# 2EDL23.net
KiCad netlist of a schematic drawn in Altium Designer
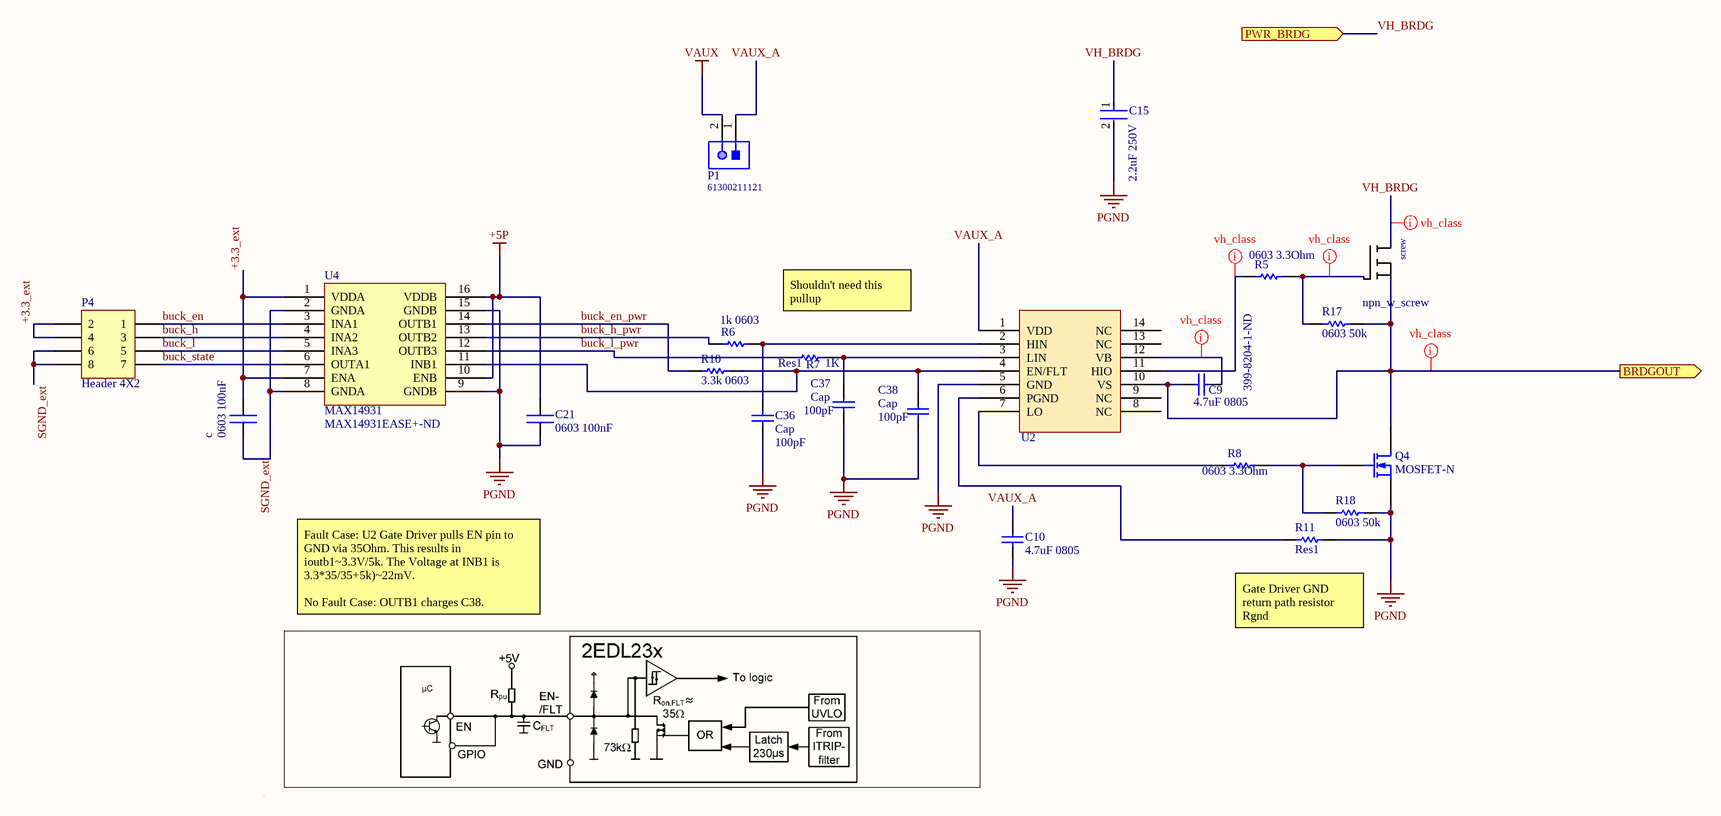
[diagram p0: 2EDL23.SchDoc]

(export (version "E")
  (design (tool "Eeschema 10.0.6"))
  (components
    (comp (ref "c")
      (value "0603 100nF")
      (footprint "CAP 0603_1608")
      (libsource (lib "coil_driver_lib") (part "cap_smd"))
    )
    (comp (ref "C9")
      (value "4.7uF 0805")
      (footprint "CAP 1206_3216 - 0.8MM")
      (description "Capacitor")
      (fields
        (field (name "SUPPLIER PART NUMBER 1") "399-8204-1-ND")
        (field (name "PUBLISHER") "Altium Limited")
      )
      (libsource (lib "Miscellaneous Devices") (part "Cap"))
    )
    (comp (ref "C10")
      (value "4.7uF 0805")
      (footprint "CAP 0805_2012")
      (description "Capacitor")
      (fields (field (name "PUBLISHER") "Altium Limited"))
      (libsource (lib "Miscellaneous Devices") (part "Cap"))
    )
    (comp (ref "C15")
      (value "2.2uF 250V")
      (footprint "FP-CGA9P-IPC_B")
      (description "Cap Ceramic 2.2uF 250V X7T 20% Pad SMD 2220 +125°C Automotive T/R\r\nCGA9P3X7T2E225M250KE")
      (fields (field (name "TOLERANCE") "20%"))
      (libsource (lib "Altium Content Vault") (part "b4654b650e69147ec39a6b967a45e02"))
    )
    (comp (ref "C21")
      (value "0603 100nF")
      (footprint "CAP 0603_1608")
      (libsource (lib "coil_driver_lib") (part "cap_smd"))
    )
    (comp (ref "C36")
      (value "Cap")
      (footprint "CAP 0603_1608")
      (description "Capacitor")
      (fields (field (name "ALTIUM_VALUE") "100pF") (field (name "PUBLISHER") "Altium Limited"))
      (libsource (lib "Miscellaneous Devices") (part "Cap"))
    )
    (comp (ref "C37")
      (value "Cap")
      (footprint "CAP 0603_1608")
      (description "Capacitor")
      (fields (field (name "ALTIUM_VALUE") "100pF") (field (name "PUBLISHER") "Altium Limited"))
      (libsource (lib "Miscellaneous Devices") (part "Cap"))
    )
    (comp (ref "C38")
      (value "Cap")
      (footprint "CAP 0603_1608")
      (description "Capacitor")
      (fields (field (name "ALTIUM_VALUE") "100pF") (field (name "PUBLISHER") "Altium Limited"))
      (libsource (lib "Miscellaneous Devices") (part "Cap"))
    )
    (comp (ref "P1")
      (value "61300211121")
      (footprint "61300211121")
      (description "THT Vertical Pin Header WR-PHD, Pitch 2.54 mm, Single Row, 2 pins")
      (fields (field (name "MANUFACTURER") "Wurth Elektronik") (field (name "PUBLISHER") "WurthElektronik"))
      (libsource (lib "Altium Content Vault") (part "WE-CN-1P-M-R2"))
    )
    (comp (ref "P4")
      (value "Header 4X2")
      (footprint "HEADER_4_2")
      (description "Header, 4-Pin, Dual row")
      (fields (field (name "PUBLISHER") "Altium Limited"))
      (libsource (lib "Miscellaneous Connectors") (part "Header 4X2"))
    )
    (comp (ref "Q3")
      (value "npn_w_screw")
      (footprint "TO-220_3_bent")
      (libsource (lib "coil_driver_lib") (part "npn_w_screw"))
    )
    (comp (ref "Q4")
      (value "MOSFET-N")
      (footprint "TO-220_3_bent")
      (description "N-Channel MOSFET")
      (fields (field (name "PUBLISHER") "Altium Limited"))
      (libsource (lib "Miscellaneous Devices") (part "MOSFET-N"))
    )
    (comp (ref "R5")
      (value "0603 3.3Ohm")
      (footprint "RES 1206_3216")
      (description "Resistor")
      (fields (field (name "PUBLISHER") "Altium Limited"))
      (libsource (lib "Miscellaneous Devices") (part "Res1"))
    )
    (comp (ref "R6")
      (value "1k 0603")
      (footprint "RES 0603_1608")
      (description "Resistor")
      (fields (field (name "PUBLISHER") "Altium Limited"))
      (libsource (lib "Miscellaneous Devices") (part "Res1"))
    )
    (comp (ref "R7")
      (value "Res1")
      (footprint "RES 0603_1608")
      (description "Resistor")
      (fields (field (name "ALTIUM_VALUE") "1K") (field (name "PUBLISHER") "Altium Limited"))
      (libsource (lib "Miscellaneous Devices") (part "Res1"))
    )
    (comp (ref "R8")
      (value "0603 3.3Ohm")
      (footprint "RES 1206_3216")
      (description "Resistor")
      (fields (field (name "PUBLISHER") "Altium Limited"))
      (libsource (lib "Miscellaneous Devices") (part "Res1"))
    )
    (comp (ref "R10")
      (value "3.3k 0603")
      (footprint "RES 0603_1608")
      (description "Resistor")
      (fields (field (name "PUBLISHER") "Altium Limited"))
      (libsource (lib "Miscellaneous Devices") (part "Res1"))
    )
    (comp (ref "R11")
      (value "Res1")
      (footprint "RES 0805_2012")
      (description "Resistor")
      (fields (field (name "PUBLISHER") "Altium Limited"))
      (libsource (lib "Miscellaneous Devices") (part "Res1"))
    )
    (comp (ref "R17")
      (value "0603 50k")
      (footprint "RES 0603_1608")
      (fields (field (name "PUBLISHER") "Altium Limited"))
      (libsource (lib "Miscellaneous Devices") (part "Res1"))
    )
    (comp (ref "R18")
      (value "0603 50k")
      (footprint "RES 0603_1608")
      (fields (field (name "PUBLISHER") "Altium Limited"))
      (libsource (lib "Miscellaneous Devices") (part "Res1"))
    )
    (comp (ref "U2")
      (value "-")
      (footprint "2EDL23I06PJ")
      (libsource (lib "coil_driver_lib") (part "2EDL23I06PJ"))
    )
    (comp (ref "U4")
      (value "MAX14931")
      (footprint "SOP16_narrow")
      (fields (field (name "SUPPLIER PART NUMBER 1") "MAX14931EASE+-ND"))
      (libsource (lib "coil_driver_lib") (part "MAX14931"))
    )
  )
  (nets
    (net (code "1") (name "+5P") (class "Default")
      (node (ref "C21") (pin "1") (pinfunction "1_1") (pintype "passive"))
      (node (ref "U4") (pin "10") (pinfunction "ENB_10") (pintype "passive"))
      (node (ref "U4") (pin "16") (pinfunction "VDDB_16") (pintype "passive"))
    )
    (net (code "2") (name "/+3.3_ext") (class "Default")
      (node (ref "P4") (pin "2") (pinfunction "2_2") (pintype "passive"))
      (node (ref "P4") (pin "4") (pinfunction "4_4") (pintype "passive"))
      (node (ref "U4") (pin "1") (pinfunction "VDDA_1") (pintype "passive"))
      (node (ref "U4") (pin "7") (pinfunction "ENA_7") (pintype "passive"))
      (node (ref "c") (pin "1") (pinfunction "1_1") (pintype "passive"))
    )
    (net (code "3") (name "/BRDGOUT") (class "Default")
      (node (ref "C9") (pin "1") (pinfunction "1_1") (pintype "passive"))
      (node (ref "Q3") (pin "3") (pinfunction "3_3") (pintype "passive"))
      (node (ref "Q4") (pin "1") (pinfunction "D_1") (pintype "passive"))
      (node (ref "R17") (pin "2") (pinfunction "2_2") (pintype "passive"))
      (node (ref "U2") (pin "10") (pinfunction "VS_10") (pintype "passive"))
    )
    (net (code "4") (name "/SGND_ext") (class "Default")
      (node (ref "P4") (pin "6") (pinfunction "6_6") (pintype "passive"))
      (node (ref "P4") (pin "8") (pinfunction "8_8") (pintype "passive"))
      (node (ref "U4") (pin "2") (pinfunction "GNDA_2") (pintype "passive"))
      (node (ref "U4") (pin "8") (pinfunction "GNDA_8") (pintype "passive"))
      (node (ref "c") (pin "2") (pinfunction "2_2") (pintype "passive"))
    )
    (net (code "5") (name "/VAUX_A") (class "Default")
      (node (ref "C10") (pin "2") (pinfunction "2_2") (pintype "passive"))
      (node (ref "P1") (pin "1") (pinfunction "1_1") (pintype "passive"))
      (node (ref "U2") (pin "1") (pinfunction "VDD_1") (pintype "passive"))
    )
    (net (code "6") (name "/VH_BRDG") (class "Default")
      (node (ref "C15") (pin "1") (pinfunction "1_1") (pintype "passive"))
      (node (ref "Q3") (pin "1") (pinfunction "1_1") (pintype "passive"))
    )
    (net (code "7") (name "/buck_en") (class "Default")
      (node (ref "P4") (pin "1") (pinfunction "1_1") (pintype "passive"))
      (node (ref "U4") (pin "3") (pinfunction "INA1_3") (pintype "passive"))
    )
    (net (code "8") (name "/buck_en_pwr") (class "Default")
      (node (ref "R10") (pin "2") (pinfunction "2_2") (pintype "passive"))
      (node (ref "U4") (pin "14") (pinfunction "OUTB1_14") (pintype "passive"))
    )
    (net (code "9") (name "/buck_h") (class "Default")
      (node (ref "P4") (pin "3") (pinfunction "3_3") (pintype "passive"))
      (node (ref "U4") (pin "4") (pinfunction "INA2_4") (pintype "passive"))
    )
    (net (code "10") (name "/buck_h_pwr") (class "Default")
      (node (ref "R6") (pin "1") (pinfunction "1_1") (pintype "passive"))
      (node (ref "U4") (pin "13") (pinfunction "OUTB2_13") (pintype "passive"))
    )
    (net (code "11") (name "/buck_l") (class "Default")
      (node (ref "P4") (pin "5") (pinfunction "5_5") (pintype "passive"))
      (node (ref "U4") (pin "5") (pinfunction "INA3_5") (pintype "passive"))
    )
    (net (code "12") (name "/buck_l_pwr") (class "Default")
      (node (ref "R7") (pin "1") (pinfunction "1_1") (pintype "passive"))
      (node (ref "U4") (pin "12") (pinfunction "OUTB3_12") (pintype "passive"))
    )
    (net (code "13") (name "/buck_state") (class "Default")
      (node (ref "P4") (pin "7") (pinfunction "7_7") (pintype "passive"))
      (node (ref "U4") (pin "6") (pinfunction "OUTA1_6") (pintype "passive"))
    )
    (net (code "14") (name "Net-(Q3-Pad2)") (class "Default")
      (node (ref "Q3") (pin "2") (pinfunction "2_2") (pintype "passive"))
      (node (ref "R17") (pin "1") (pinfunction "1_1") (pintype "passive"))
      (node (ref "R5") (pin "2") (pinfunction "2_2") (pintype "passive"))
    )
    (net (code "15") (name "Net-(Q4-G)") (class "Default")
      (node (ref "Q4") (pin "2") (pinfunction "G_2") (pintype "passive"))
      (node (ref "R18") (pin "1") (pinfunction "1_1") (pintype "passive"))
      (node (ref "R8") (pin "2") (pinfunction "2_2") (pintype "passive"))
    )
    (net (code "16") (name "Net-(U2-EN{slash}FLT)") (class "Default")
      (node (ref "C38") (pin "2") (pinfunction "2_2") (pintype "passive"))
      (node (ref "R10") (pin "1") (pinfunction "1_1") (pintype "passive"))
      (node (ref "U2") (pin "4") (pinfunction "EN/FLT_4") (pintype "passive"))
      (node (ref "U4") (pin "11") (pinfunction "INB1_11") (pintype "passive"))
    )
    (net (code "17") (name "Net-(U2-HIN)") (class "Default")
      (node (ref "C36") (pin "2") (pinfunction "2_2") (pintype "passive"))
      (node (ref "R6") (pin "2") (pinfunction "2_2") (pintype "passive"))
      (node (ref "U2") (pin "2") (pinfunction "HIN_2") (pintype "passive"))
    )
    (net (code "18") (name "Net-(U2-HIO)") (class "Default")
      (node (ref "R5") (pin "1") (pinfunction "1_1") (pintype "passive"))
      (node (ref "U2") (pin "11") (pinfunction "HIO_11") (pintype "passive"))
    )
    (net (code "19") (name "Net-(U2-LIN)") (class "Default")
      (node (ref "C37") (pin "2") (pinfunction "2_2") (pintype "passive"))
      (node (ref "R7") (pin "2") (pinfunction "2_2") (pintype "passive"))
      (node (ref "U2") (pin "3") (pinfunction "LIN_3") (pintype "passive"))
    )
    (net (code "20") (name "Net-(U2-LO)") (class "Default")
      (node (ref "R8") (pin "1") (pinfunction "1_1") (pintype "passive"))
      (node (ref "U2") (pin "7") (pinfunction "LO_7") (pintype "passive"))
    )
    (net (code "21") (name "Net-(U2-PGND)") (class "Default")
      (node (ref "R11") (pin "1") (pinfunction "1_1") (pintype "passive"))
      (node (ref "U2") (pin "6") (pinfunction "PGND_6") (pintype "passive"))
    )
    (net (code "22") (name "Net-(U2-VB)") (class "Default")
      (node (ref "C9") (pin "2") (pinfunction "2_2") (pintype "passive"))
      (node (ref "U2") (pin "12") (pinfunction "VB_12") (pintype "passive"))
    )
    (net (code "23") (name "PGND") (class "Default")
      (node (ref "C10") (pin "1") (pinfunction "1_1") (pintype "passive"))
      (node (ref "C15") (pin "2") (pinfunction "2_2") (pintype "passive"))
      (node (ref "C21") (pin "2") (pinfunction "2_2") (pintype "passive"))
      (node (ref "C36") (pin "1") (pinfunction "1_1") (pintype "passive"))
      (node (ref "C37") (pin "1") (pinfunction "1_1") (pintype "passive"))
      (node (ref "C38") (pin "1") (pinfunction "1_1") (pintype "passive"))
      (node (ref "Q4") (pin "3") (pinfunction "S_3") (pintype "passive"))
      (node (ref "R11") (pin "2") (pinfunction "2_2") (pintype "passive"))
      (node (ref "R18") (pin "2") (pinfunction "2_2") (pintype "passive"))
      (node (ref "U2") (pin "5") (pinfunction "GND_5") (pintype "passive"))
      (node (ref "U4") (pin "15") (pinfunction "GNDB_15") (pintype "passive"))
      (node (ref "U4") (pin "9") (pinfunction "GNDB_9") (pintype "passive"))
    )
    (net (code "24") (name "VAUX") (class "Default")
      (node (ref "P1") (pin "2") (pinfunction "2_2") (pintype "passive"))
    )
    (net (code "25") (name "unconnected-(Q3-screw-Pad4)") (class "Default")
      (node (ref "Q3") (pin "4") (pinfunction "screw_4") (pintype "passive"))
    )
    (net (code "26") (name "unconnected-(U2-NC-Pad8)") (class "Default")
      (node (ref "U2") (pin "8") (pinfunction "NC_8") (pintype "passive"))
    )
    (net (code "27") (name "unconnected-(U2-NC-Pad9)") (class "Default")
      (node (ref "U2") (pin "9") (pinfunction "NC_9") (pintype "passive"))
    )
    (net (code "28") (name "unconnected-(U2-NC-Pad13)") (class "Default")
      (node (ref "U2") (pin "13") (pinfunction "NC_13") (pintype "passive"))
    )
    (net (code "29") (name "unconnected-(U2-NC-Pad14)") (class "Default")
      (node (ref "U2") (pin "14") (pinfunction "NC_14") (pintype "passive"))
    )
  )
)
